# chariot_power.net
KiCad netlist of a schematic drawn in EAGLE
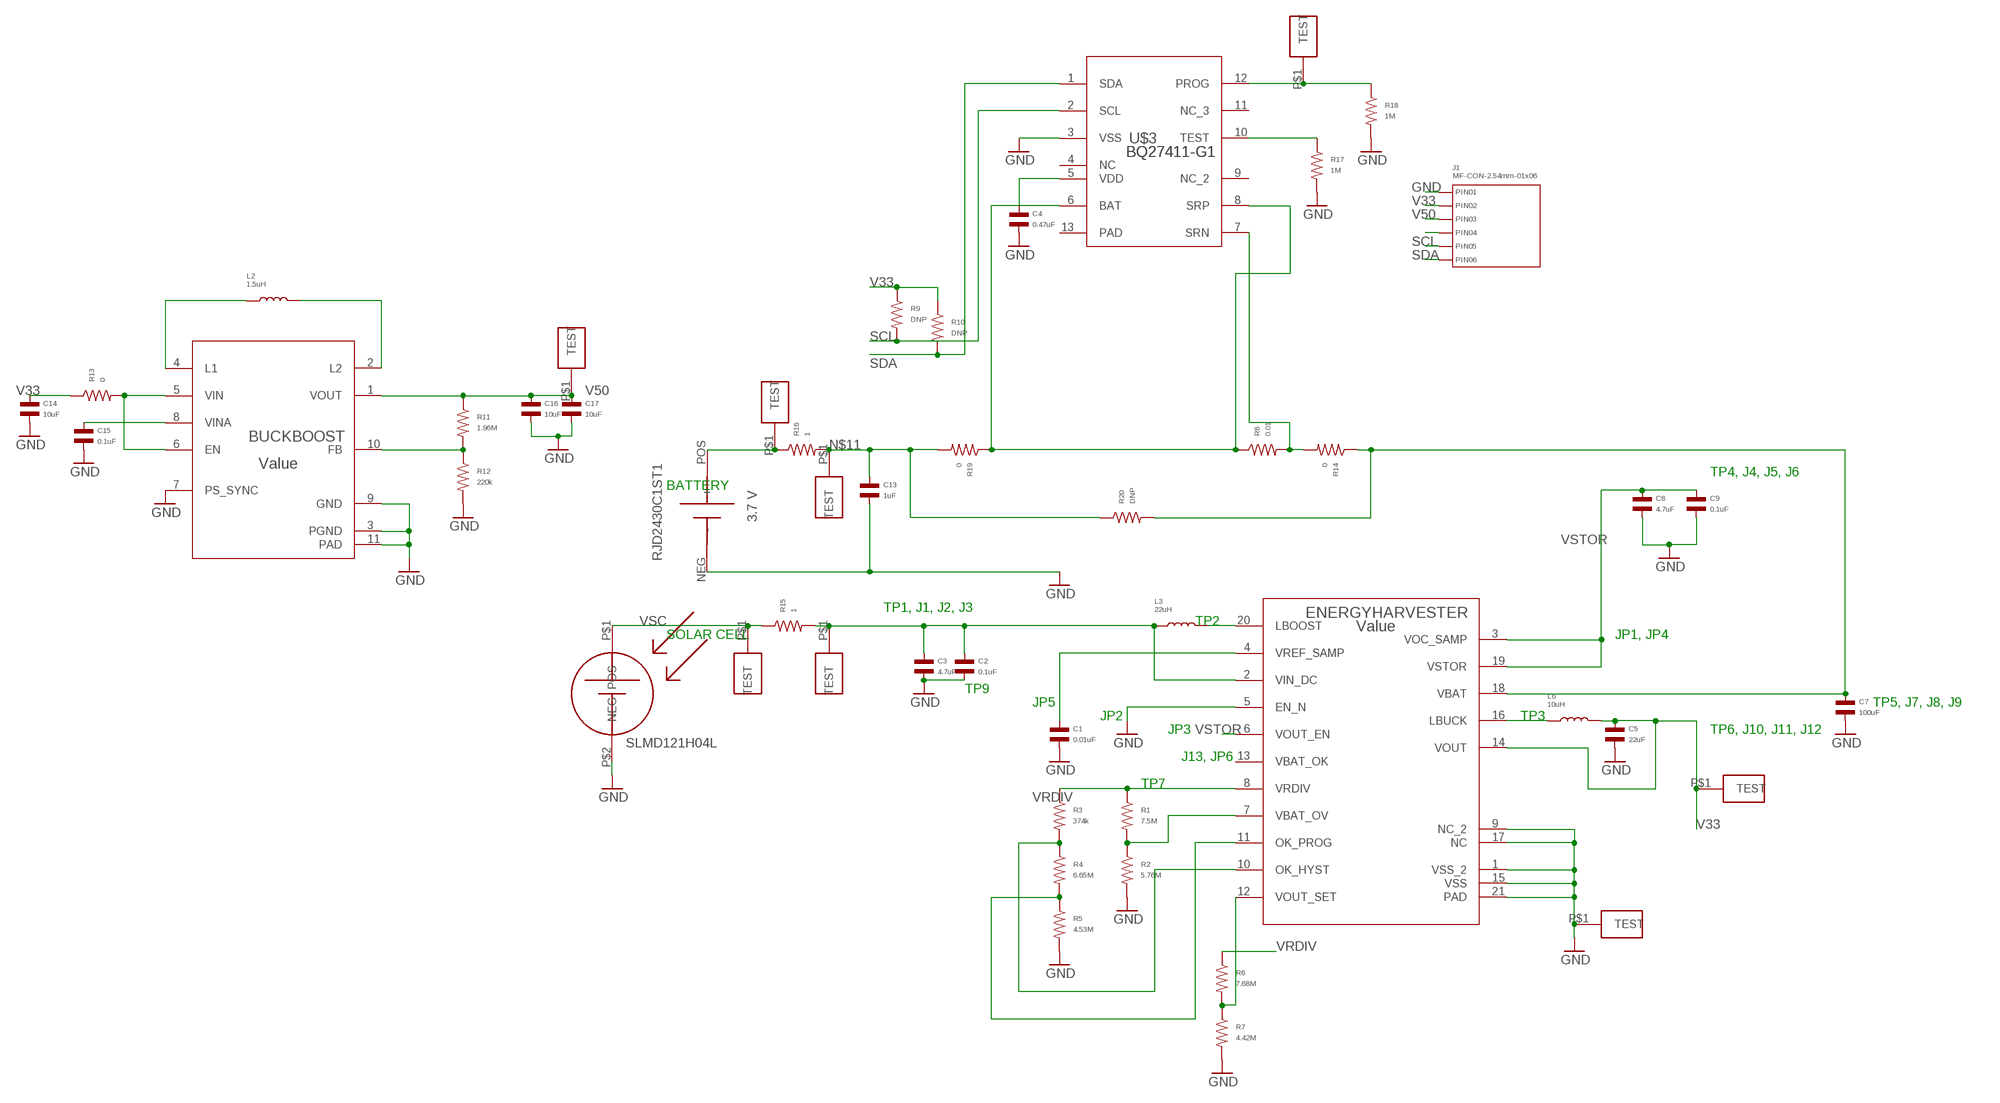
[diagram p0: schematic, sheet 1]

(export (version "E")
  (design (tool "Eeschema 10.0.6"))
  (components
    (comp (ref "BUCKBOOST")
      (value "Value")
      (footprint "eagle-import:DSK0010A")
      (fields (field (name "MANUFACTURER") "Texas Instruments") (field (name "PARTNUMBER") "TPS63030DSK"))
      (libsource (lib "eagle-import") (part "TPS63030DSKR"))
    )
    (comp (ref "C1")
      (value "0.01uF")
      (footprint "eagle-import:C0603")
      (libsource (lib "eagle-import") (part "CAPACITOR_NP_0603"))
    )
    (comp (ref "C2")
      (value "0.1uF")
      (footprint "eagle-import:C0603")
      (libsource (lib "eagle-import") (part "CAPACITOR_NP_0603"))
    )
    (comp (ref "C3")
      (value "4.7uF")
      (footprint "eagle-import:C0603")
      (libsource (lib "eagle-import") (part "CAPACITOR_NP_0603"))
    )
    (comp (ref "C4")
      (value "0.47uF")
      (footprint "eagle-import:C0603")
      (libsource (lib "eagle-import") (part "CAPACITOR_NP_0603"))
    )
    (comp (ref "C5")
      (value "22uF")
      (footprint "eagle-import:C0603")
      (libsource (lib "eagle-import") (part "CAPACITOR_NP_0603"))
    )
    (comp (ref "C7")
      (value "100uF")
      (footprint "eagle-import:C0603")
      (libsource (lib "eagle-import") (part "CAPACITOR_NP_0603"))
    )
    (comp (ref "C8")
      (value "4.7uF")
      (footprint "eagle-import:C0603")
      (libsource (lib "eagle-import") (part "CAPACITOR_NP_0603"))
    )
    (comp (ref "C9")
      (value "0.1uF")
      (footprint "eagle-import:C0603")
      (libsource (lib "eagle-import") (part "CAPACITOR_NP_0603"))
    )
    (comp (ref "C13")
      (value "1uF")
      (footprint "eagle-import:C0603")
      (libsource (lib "eagle-import") (part "CAPACITOR_NP_0603"))
    )
    (comp (ref "C14")
      (value "10uF")
      (footprint "eagle-import:C0603")
      (libsource (lib "eagle-import") (part "CAPACITOR_NP_0603"))
    )
    (comp (ref "C15")
      (value "0.1uF")
      (footprint "eagle-import:C0603")
      (libsource (lib "eagle-import") (part "CAPACITOR_NP_0603"))
    )
    (comp (ref "C16")
      (value "10uF")
      (footprint "eagle-import:C0603")
      (libsource (lib "eagle-import") (part "CAPACITOR_NP_0603"))
    )
    (comp (ref "C17")
      (value "10uF")
      (footprint "eagle-import:C0603")
      (libsource (lib "eagle-import") (part "CAPACITOR_NP_0603"))
    )
    (comp (ref "ENERGYHARVESTER")
      (value "Value")
      (footprint "eagle-import:RGR0020A")
      (fields
        (field (name "ALTERNATEPARTNUMBER") "BQ25570RGRT")
        (field (name "MANUFACTURER") "Texas Instruments")
        (field (name "PARTNUMBER") "BQ25570RGRR")
      )
      (libsource (lib "eagle-import") (part "BQ25570RGRR"))
    )
    (comp (ref "J1")
      (value "MF-CON-2.54mm-01x06")
      (footprint "eagle-import:PTH_2.54MM_01X06")
      (fields (field (name "HOUSEPART") "YES"))
      (libsource (lib "eagle-import") (part "CON_01X06_PTH_2.54MM"))
    )
    (comp (ref "L2")
      (value "1.5uH")
      (footprint "eagle-import:L0603")
      (libsource (lib "eagle-import") (part "INDUCTOR_0603"))
    )
    (comp (ref "L3")
      (value "22uH")
      (footprint "eagle-import:L0603")
      (libsource (lib "eagle-import") (part "INDUCTOR_0603"))
    )
    (comp (ref "L6")
      (value "10uH")
      (footprint "eagle-import:L0603")
      (libsource (lib "eagle-import") (part "INDUCTOR_0603"))
    )
    (comp (ref "R1")
      (value "7.5M")
      (footprint "eagle-import:R0603")
      (libsource (lib "eagle-import") (part "RESISTOR_0603"))
    )
    (comp (ref "R2")
      (value "5.76M")
      (footprint "eagle-import:R0603")
      (libsource (lib "eagle-import") (part "RESISTOR_0603"))
    )
    (comp (ref "R3")
      (value "374k")
      (footprint "eagle-import:R0603")
      (libsource (lib "eagle-import") (part "RESISTOR_0603"))
    )
    (comp (ref "R4")
      (value "6.65M")
      (footprint "eagle-import:R0603")
      (libsource (lib "eagle-import") (part "RESISTOR_0603"))
    )
    (comp (ref "R5")
      (value "4.53M")
      (footprint "eagle-import:R0603")
      (libsource (lib "eagle-import") (part "RESISTOR_0603"))
    )
    (comp (ref "R6")
      (value "7.68M")
      (footprint "eagle-import:R0603")
      (libsource (lib "eagle-import") (part "RESISTOR_0603"))
    )
    (comp (ref "R7")
      (value "4.42M")
      (footprint "eagle-import:R0603")
      (libsource (lib "eagle-import") (part "RESISTOR_0603"))
    )
    (comp (ref "R8")
      (value "0.01")
      (footprint "eagle-import:R0603")
      (libsource (lib "eagle-import") (part "RESISTOR_0603"))
    )
    (comp (ref "R9")
      (value "DNP")
      (footprint "eagle-import:R0603")
      (libsource (lib "eagle-import") (part "RESISTOR_0603"))
    )
    (comp (ref "R10")
      (value "DNP")
      (footprint "eagle-import:R0603")
      (libsource (lib "eagle-import") (part "RESISTOR_0603"))
    )
    (comp (ref "R11")
      (value "1.96M")
      (footprint "eagle-import:R0603")
      (libsource (lib "eagle-import") (part "RESISTOR_0603"))
    )
    (comp (ref "R12")
      (value "220k")
      (footprint "eagle-import:R0603")
      (libsource (lib "eagle-import") (part "RESISTOR_0603"))
    )
    (comp (ref "R13")
      (value "0")
      (footprint "eagle-import:R0603")
      (libsource (lib "eagle-import") (part "RESISTOR_0603"))
    )
    (comp (ref "R14")
      (value "0")
      (footprint "eagle-import:R0603")
      (libsource (lib "eagle-import") (part "RESISTOR_0603"))
    )
    (comp (ref "R15")
      (value "1")
      (footprint "eagle-import:R0603")
      (libsource (lib "eagle-import") (part "RESISTOR_0603"))
    )
    (comp (ref "R16")
      (value "1")
      (footprint "eagle-import:R0603")
      (libsource (lib "eagle-import") (part "RESISTOR_0603"))
    )
    (comp (ref "R17")
      (value "1M")
      (footprint "eagle-import:R0603")
      (libsource (lib "eagle-import") (part "RESISTOR_0603"))
    )
    (comp (ref "R18")
      (value "1M")
      (footprint "eagle-import:R0603")
      (libsource (lib "eagle-import") (part "RESISTOR_0603"))
    )
    (comp (ref "R19")
      (value "0")
      (footprint "eagle-import:R0603")
      (libsource (lib "eagle-import") (part "RESISTOR_0603"))
    )
    (comp (ref "R20")
      (value "DNP")
      (footprint "eagle-import:R0603")
      (libsource (lib "eagle-import") (part "RESISTOR_0603"))
    )
    (comp (ref "TP1")
      (value "TESTPOINT_LOOP")
      (footprint "eagle-import:TESTPOINT_LOOP")
      (libsource (lib "eagle-import") (part "TESTPOINT_LOOP"))
    )
    (comp (ref "TP2")
      (value "TESTPOINT_LOOP")
      (footprint "eagle-import:TESTPOINT_LOOP")
      (libsource (lib "eagle-import") (part "TESTPOINT_LOOP"))
    )
    (comp (ref "TP3")
      (value "TESTPOINT_LOOP")
      (footprint "eagle-import:TESTPOINT_LOOP")
      (libsource (lib "eagle-import") (part "TESTPOINT_LOOP"))
    )
    (comp (ref "TP4")
      (value "TESTPOINT_LOOP")
      (footprint "eagle-import:TESTPOINT_LOOP")
      (libsource (lib "eagle-import") (part "TESTPOINT_LOOP"))
    )
    (comp (ref "TP5")
      (value "TESTPOINT_LOOP")
      (footprint "eagle-import:TESTPOINT_LOOP")
      (libsource (lib "eagle-import") (part "TESTPOINT_LOOP"))
    )
    (comp (ref "TP6")
      (value "TESTPOINT_LOOP")
      (footprint "eagle-import:TESTPOINT_LOOP")
      (libsource (lib "eagle-import") (part "TESTPOINT_LOOP"))
    )
    (comp (ref "TP7")
      (value "TESTPOINT_LOOP")
      (footprint "eagle-import:TESTPOINT_LOOP")
      (libsource (lib "eagle-import") (part "TESTPOINT_LOOP"))
    )
    (comp (ref "TP8")
      (value "TESTPOINT_LOOP")
      (footprint "eagle-import:TESTPOINT_LOOP")
      (libsource (lib "eagle-import") (part "TESTPOINT_LOOP"))
    )
    (comp (ref "U$1")
      (value "SLMD121H04L")
      (footprint "eagle-import:SLMD121H04L")
      (libsource (lib "eagle-import") (part "SLMD121H04L"))
    )
    (comp (ref "U$2")
      (value "RJD2430C1ST1.")
      (footprint "eagle-import:RJD2430C1ST1")
      (libsource (lib "eagle-import") (part "RJD2430C1ST1."))
    )
    (comp (ref "U$3")
      (value "BQ27411-G1")
      (footprint "eagle-import:DRZ0012A")
      (libsource (lib "eagle-import") (part "BQ27411-G1"))
    )
  )
  (nets
    (net (code "1") (name "/N$11") (class "Default")
      (node (ref "C13") (pin "P$1") (pinfunction "P$1_P$1") (pintype "passive"))
      (node (ref "R16") (pin "P$2") (pinfunction "P$2_P$2") (pintype "passive"))
      (node (ref "R19") (pin "P$2") (pinfunction "P$2_P$2") (pintype "passive"))
      (node (ref "R20") (pin "P$1") (pinfunction "P$1_P$1") (pintype "passive"))
      (node (ref "TP7") (pin "P$1") (pinfunction "TEST_P$1") (pintype "bidirectional"))
    )
    (net (code "2") (name "/SCL") (class "Default")
      (node (ref "J1") (pin "P$5") (pinfunction "PIN5_P$5") (pintype "bidirectional"))
      (node (ref "R9") (pin "P$2") (pinfunction "P$2_P$2") (pintype "passive"))
      (node (ref "U$3") (pin "2") (pinfunction "SCL_2") (pintype "bidirectional"))
    )
    (net (code "3") (name "/SDA") (class "Default")
      (node (ref "J1") (pin "P$6") (pinfunction "PIN6_P$6") (pintype "bidirectional"))
      (node (ref "R10") (pin "P$2") (pinfunction "P$2_P$2") (pintype "passive"))
      (node (ref "U$3") (pin "1") (pinfunction "SDA_1") (pintype "bidirectional"))
    )
    (net (code "4") (name "/V33") (class "Default")
      (node (ref "BUCKBOOST") (pin "5") (pinfunction "VIN_5") (pintype "power_in"))
      (node (ref "BUCKBOOST") (pin "6") (pinfunction "EN_6") (pintype "input"))
      (node (ref "C5") (pin "P$1") (pinfunction "P$1_P$1") (pintype "passive"))
      (node (ref "ENERGYHARVESTER") (pin "14") (pinfunction "VOUT_14") (pintype "power_in"))
      (node (ref "J1") (pin "P$2") (pinfunction "PIN2_P$2") (pintype "bidirectional"))
      (node (ref "L6") (pin "P$2") (pinfunction "P$2_P$2") (pintype "passive"))
      (node (ref "R10") (pin "P$1") (pinfunction "P$1_P$1") (pintype "passive"))
      (node (ref "R13") (pin "P$2") (pinfunction "P$2_P$2") (pintype "passive"))
      (node (ref "R9") (pin "P$1") (pinfunction "P$1_P$1") (pintype "passive"))
      (node (ref "TP2") (pin "P$1") (pinfunction "TEST_P$1") (pintype "bidirectional"))
    )
    (net (code "5") (name "/V50") (class "Default")
      (node (ref "BUCKBOOST") (pin "1") (pinfunction "VOUT_1") (pintype "power_in"))
      (node (ref "C16") (pin "P$1") (pinfunction "P$1_P$1") (pintype "passive"))
      (node (ref "C17") (pin "P$1") (pinfunction "P$1_P$1") (pintype "passive"))
      (node (ref "J1") (pin "P$3") (pinfunction "PIN3_P$3") (pintype "bidirectional"))
      (node (ref "R11") (pin "P$1") (pinfunction "P$1_P$1") (pintype "passive"))
      (node (ref "TP3") (pin "P$1") (pinfunction "TEST_P$1") (pintype "bidirectional"))
    )
    (net (code "6") (name "/VRDIV") (class "Default")
      (node (ref "ENERGYHARVESTER") (pin "8") (pinfunction "VRDIV_8") (pintype "output"))
      (node (ref "R1") (pin "P$1") (pinfunction "P$1_P$1") (pintype "passive"))
      (node (ref "R3") (pin "P$1") (pinfunction "P$1_P$1") (pintype "passive"))
      (node (ref "R6") (pin "P$1") (pinfunction "P$1_P$1") (pintype "passive"))
    )
    (net (code "7") (name "/VSC") (class "Default")
      (node (ref "R15") (pin "P$1") (pinfunction "P$1_P$1") (pintype "passive"))
      (node (ref "TP4") (pin "P$1") (pinfunction "TEST_P$1") (pintype "bidirectional"))
      (node (ref "U$1") (pin "P$1") (pinfunction "POS_P$1") (pintype "bidirectional"))
    )
    (net (code "8") (name "/VSTOR") (class "Default")
      (node (ref "C8") (pin "P$1") (pinfunction "P$1_P$1") (pintype "passive"))
      (node (ref "C9") (pin "P$1") (pinfunction "P$1_P$1") (pintype "passive"))
      (node (ref "ENERGYHARVESTER") (pin "19") (pinfunction "VSTOR_19") (pintype "power_in"))
      (node (ref "ENERGYHARVESTER") (pin "3") (pinfunction "VOC_SAMP_3") (pintype "input"))
      (node (ref "ENERGYHARVESTER") (pin "6") (pinfunction "VOUT_EN_6") (pintype "input"))
    )
    (net (code "9") (name "GND") (class "Default")
      (node (ref "BUCKBOOST") (pin "11") (pinfunction "PAD_11") (pintype "power_in"))
      (node (ref "BUCKBOOST") (pin "3") (pinfunction "PGND_3") (pintype "power_in"))
      (node (ref "BUCKBOOST") (pin "7") (pinfunction "PS_SYNC_7") (pintype "input"))
      (node (ref "BUCKBOOST") (pin "9") (pinfunction "GND_9") (pintype "power_in"))
      (node (ref "C1") (pin "P$2") (pinfunction "P$2_P$2") (pintype "passive"))
      (node (ref "C13") (pin "P$2") (pinfunction "P$2_P$2") (pintype "passive"))
      (node (ref "C14") (pin "P$2") (pinfunction "P$2_P$2") (pintype "passive"))
      (node (ref "C15") (pin "P$2") (pinfunction "P$2_P$2") (pintype "passive"))
      (node (ref "C16") (pin "P$2") (pinfunction "P$2_P$2") (pintype "passive"))
      (node (ref "C17") (pin "P$2") (pinfunction "P$2_P$2") (pintype "passive"))
      (node (ref "C2") (pin "P$2") (pinfunction "P$2_P$2") (pintype "passive"))
      (node (ref "C3") (pin "P$2") (pinfunction "P$2_P$2") (pintype "passive"))
      (node (ref "C4") (pin "P$2") (pinfunction "P$2_P$2") (pintype "passive"))
      (node (ref "C5") (pin "P$2") (pinfunction "P$2_P$2") (pintype "passive"))
      (node (ref "C7") (pin "P$2") (pinfunction "P$2_P$2") (pintype "passive"))
      (node (ref "C8") (pin "P$2") (pinfunction "P$2_P$2") (pintype "passive"))
      (node (ref "C9") (pin "P$2") (pinfunction "P$2_P$2") (pintype "passive"))
      (node (ref "ENERGYHARVESTER") (pin "1") (pinfunction "VSS_2_1") (pintype "power_in"))
      (node (ref "ENERGYHARVESTER") (pin "15") (pinfunction "VSS_15") (pintype "power_in"))
      (node (ref "ENERGYHARVESTER") (pin "17") (pinfunction "NC_17") (pintype "passive"))
      (node (ref "ENERGYHARVESTER") (pin "21") (pinfunction "PAD_21") (pintype "power_in"))
      (node (ref "ENERGYHARVESTER") (pin "5") (pinfunction "EN_N_5") (pintype "input"))
      (node (ref "ENERGYHARVESTER") (pin "9") (pinfunction "NC_2_9") (pintype "power_in"))
      (node (ref "J1") (pin "P$1") (pinfunction "PIN1_P$1") (pintype "bidirectional"))
      (node (ref "R12") (pin "P$2") (pinfunction "P$2_P$2") (pintype "passive"))
      (node (ref "R17") (pin "P$2") (pinfunction "P$2_P$2") (pintype "passive"))
      (node (ref "R18") (pin "P$2") (pinfunction "P$2_P$2") (pintype "passive"))
      (node (ref "R2") (pin "P$2") (pinfunction "P$2_P$2") (pintype "passive"))
      (node (ref "R5") (pin "P$2") (pinfunction "P$2_P$2") (pintype "passive"))
      (node (ref "R7") (pin "P$2") (pinfunction "P$2_P$2") (pintype "passive"))
      (node (ref "TP1") (pin "P$1") (pinfunction "TEST_P$1") (pintype "bidirectional"))
      (node (ref "U$1") (pin "P$2") (pinfunction "NEG_P$2") (pintype "bidirectional"))
      (node (ref "U$2") (pin "NEG") (pinfunction "-_NEG") (pintype "bidirectional"))
      (node (ref "U$3") (pin "3") (pinfunction "VSS_3") (pintype "power_in"))
    )
    (net (code "10") (name "Net-(BUCKBOOST-FB)") (class "Default")
      (node (ref "BUCKBOOST") (pin "10") (pinfunction "FB_10") (pintype "input"))
      (node (ref "R11") (pin "P$2") (pinfunction "P$2_P$2") (pintype "passive"))
      (node (ref "R12") (pin "P$1") (pinfunction "P$1_P$1") (pintype "passive"))
    )
    (net (code "11") (name "Net-(BUCKBOOST-L1)") (class "Default")
      (node (ref "BUCKBOOST") (pin "4") (pinfunction "L1_4") (pintype "passive"))
      (node (ref "L2") (pin "P$1") (pinfunction "P$1_P$1") (pintype "passive"))
    )
    (net (code "12") (name "Net-(BUCKBOOST-L2)") (class "Default")
      (node (ref "BUCKBOOST") (pin "2") (pinfunction "L2_2") (pintype "passive"))
      (node (ref "L2") (pin "P$2") (pinfunction "P$2_P$2") (pintype "passive"))
    )
    (net (code "13") (name "Net-(BUCKBOOST-VINA)") (class "Default")
      (node (ref "BUCKBOOST") (pin "8") (pinfunction "VINA_8") (pintype "power_in"))
      (node (ref "C15") (pin "P$1") (pinfunction "P$1_P$1") (pintype "passive"))
    )
    (net (code "14") (name "Net-(C14-PadP$1)") (class "Default")
      (node (ref "C14") (pin "P$1") (pinfunction "P$1_P$1") (pintype "passive"))
      (node (ref "R13") (pin "P$1") (pinfunction "P$1_P$1") (pintype "passive"))
    )
    (net (code "15") (name "Net-(ENERGYHARVESTER-LBOOST)") (class "Default")
      (node (ref "ENERGYHARVESTER") (pin "20") (pinfunction "LBOOST_20") (pintype "input"))
      (node (ref "L3") (pin "P$2") (pinfunction "P$2_P$2") (pintype "passive"))
    )
    (net (code "16") (name "Net-(ENERGYHARVESTER-LBUCK)") (class "Default")
      (node (ref "ENERGYHARVESTER") (pin "16") (pinfunction "LBUCK_16") (pintype "passive"))
      (node (ref "L6") (pin "P$1") (pinfunction "P$1_P$1") (pintype "passive"))
    )
    (net (code "17") (name "Net-(ENERGYHARVESTER-OK_HYST)") (class "Default")
      (node (ref "ENERGYHARVESTER") (pin "10") (pinfunction "OK_HYST_10") (pintype "input"))
      (node (ref "R3") (pin "P$2") (pinfunction "P$2_P$2") (pintype "passive"))
      (node (ref "R4") (pin "P$1") (pinfunction "P$1_P$1") (pintype "passive"))
    )
    (net (code "18") (name "Net-(ENERGYHARVESTER-OK_PROG)") (class "Default")
      (node (ref "ENERGYHARVESTER") (pin "11") (pinfunction "OK_PROG_11") (pintype "input"))
      (node (ref "R4") (pin "P$2") (pinfunction "P$2_P$2") (pintype "passive"))
      (node (ref "R5") (pin "P$1") (pinfunction "P$1_P$1") (pintype "passive"))
    )
    (net (code "19") (name "Net-(ENERGYHARVESTER-VBAT)") (class "Default")
      (node (ref "C7") (pin "P$1") (pinfunction "P$1_P$1") (pintype "passive"))
      (node (ref "ENERGYHARVESTER") (pin "18") (pinfunction "VBAT_18") (pintype "bidirectional"))
      (node (ref "R14") (pin "P$1") (pinfunction "P$1_P$1") (pintype "passive"))
      (node (ref "R20") (pin "P$2") (pinfunction "P$2_P$2") (pintype "passive"))
    )
    (net (code "20") (name "Net-(ENERGYHARVESTER-VBAT_OV)") (class "Default")
      (node (ref "ENERGYHARVESTER") (pin "7") (pinfunction "VBAT_OV_7") (pintype "input"))
      (node (ref "R1") (pin "P$2") (pinfunction "P$2_P$2") (pintype "passive"))
      (node (ref "R2") (pin "P$1") (pinfunction "P$1_P$1") (pintype "passive"))
    )
    (net (code "21") (name "Net-(ENERGYHARVESTER-VIN_DC)") (class "Default")
      (node (ref "C2") (pin "P$1") (pinfunction "P$1_P$1") (pintype "passive"))
      (node (ref "C3") (pin "P$1") (pinfunction "P$1_P$1") (pintype "passive"))
      (node (ref "ENERGYHARVESTER") (pin "2") (pinfunction "VIN_DC_2") (pintype "power_in"))
      (node (ref "L3") (pin "P$1") (pinfunction "P$1_P$1") (pintype "passive"))
      (node (ref "R15") (pin "P$2") (pinfunction "P$2_P$2") (pintype "passive"))
      (node (ref "TP6") (pin "P$1") (pinfunction "TEST_P$1") (pintype "bidirectional"))
    )
    (net (code "22") (name "Net-(ENERGYHARVESTER-VOUT_SET)") (class "Default")
      (node (ref "ENERGYHARVESTER") (pin "12") (pinfunction "VOUT_SET_12") (pintype "input"))
      (node (ref "R6") (pin "P$2") (pinfunction "P$2_P$2") (pintype "passive"))
      (node (ref "R7") (pin "P$1") (pinfunction "P$1_P$1") (pintype "passive"))
    )
    (net (code "23") (name "Net-(ENERGYHARVESTER-VREF_SAMP)") (class "Default")
      (node (ref "C1") (pin "P$1") (pinfunction "P$1_P$1") (pintype "passive"))
      (node (ref "ENERGYHARVESTER") (pin "4") (pinfunction "VREF_SAMP_4") (pintype "input"))
    )
    (net (code "24") (name "Net-(TP5-TEST)") (class "Default")
      (node (ref "R16") (pin "P$1") (pinfunction "P$1_P$1") (pintype "passive"))
      (node (ref "TP5") (pin "P$1") (pinfunction "TEST_P$1") (pintype "bidirectional"))
      (node (ref "U$2") (pin "POS") (pinfunction "+_POS") (pintype "bidirectional"))
    )
    (net (code "25") (name "Net-(TP8-TEST)") (class "Default")
      (node (ref "R18") (pin "P$1") (pinfunction "P$1_P$1") (pintype "passive"))
      (node (ref "TP8") (pin "P$1") (pinfunction "TEST_P$1") (pintype "bidirectional"))
      (node (ref "U$3") (pin "12") (pinfunction "PROG_12") (pintype "output"))
    )
    (net (code "26") (name "Net-(U$3-BAT)") (class "Default")
      (node (ref "R19") (pin "P$1") (pinfunction "P$1_P$1") (pintype "passive"))
      (node (ref "R8") (pin "P$1") (pinfunction "P$1_P$1") (pintype "passive"))
      (node (ref "U$3") (pin "6") (pinfunction "BAT_6") (pintype "power_in"))
      (node (ref "U$3") (pin "8") (pinfunction "SRP_8") (pintype "bidirectional"))
    )
    (net (code "27") (name "Net-(U$3-SRN)") (class "Default")
      (node (ref "R14") (pin "P$2") (pinfunction "P$2_P$2") (pintype "passive"))
      (node (ref "R8") (pin "P$2") (pinfunction "P$2_P$2") (pintype "passive"))
      (node (ref "U$3") (pin "7") (pinfunction "SRN_7") (pintype "bidirectional"))
    )
    (net (code "28") (name "Net-(U$3-TEST)") (class "Default")
      (node (ref "R17") (pin "P$1") (pinfunction "P$1_P$1") (pintype "passive"))
      (node (ref "U$3") (pin "10") (pinfunction "TEST_10") (pintype "input"))
    )
    (net (code "29") (name "Net-(U$3-VDD)") (class "Default")
      (node (ref "C4") (pin "P$1") (pinfunction "P$1_P$1") (pintype "passive"))
      (node (ref "U$3") (pin "5") (pinfunction "VDD_5") (pintype "power_in"))
    )
    (net (code "30") (name "unconnected-(ENERGYHARVESTER-VBAT_OK-Pad13)") (class "Default")
      (node (ref "ENERGYHARVESTER") (pin "13") (pinfunction "VBAT_OK_13") (pintype "output"))
    )
    (net (code "31") (name "unconnected-(J1-PIN4-PadP$4)") (class "Default")
      (node (ref "J1") (pin "P$4") (pinfunction "PIN4_P$4") (pintype "bidirectional"))
    )
    (net (code "32") (name "unconnected-(U$3-NC-Pad4)") (class "Default")
      (node (ref "U$3") (pin "4") (pinfunction "NC_4") (pintype "passive"))
    )
    (net (code "33") (name "unconnected-(U$3-NC_2-Pad9)") (class "Default")
      (node (ref "U$3") (pin "9") (pinfunction "NC_2_9") (pintype "passive"))
    )
    (net (code "34") (name "unconnected-(U$3-NC_3-Pad11)") (class "Default")
      (node (ref "U$3") (pin "11") (pinfunction "NC_3_11") (pintype "passive"))
    )
    (net (code "35") (name "unconnected-(U$3-PAD-Pad13)") (class "Default")
      (node (ref "U$3") (pin "13") (pinfunction "PAD_13") (pintype "passive"))
    )
  )
)
